# Sheet.net
KiCad netlist of a schematic drawn in Altium Designer
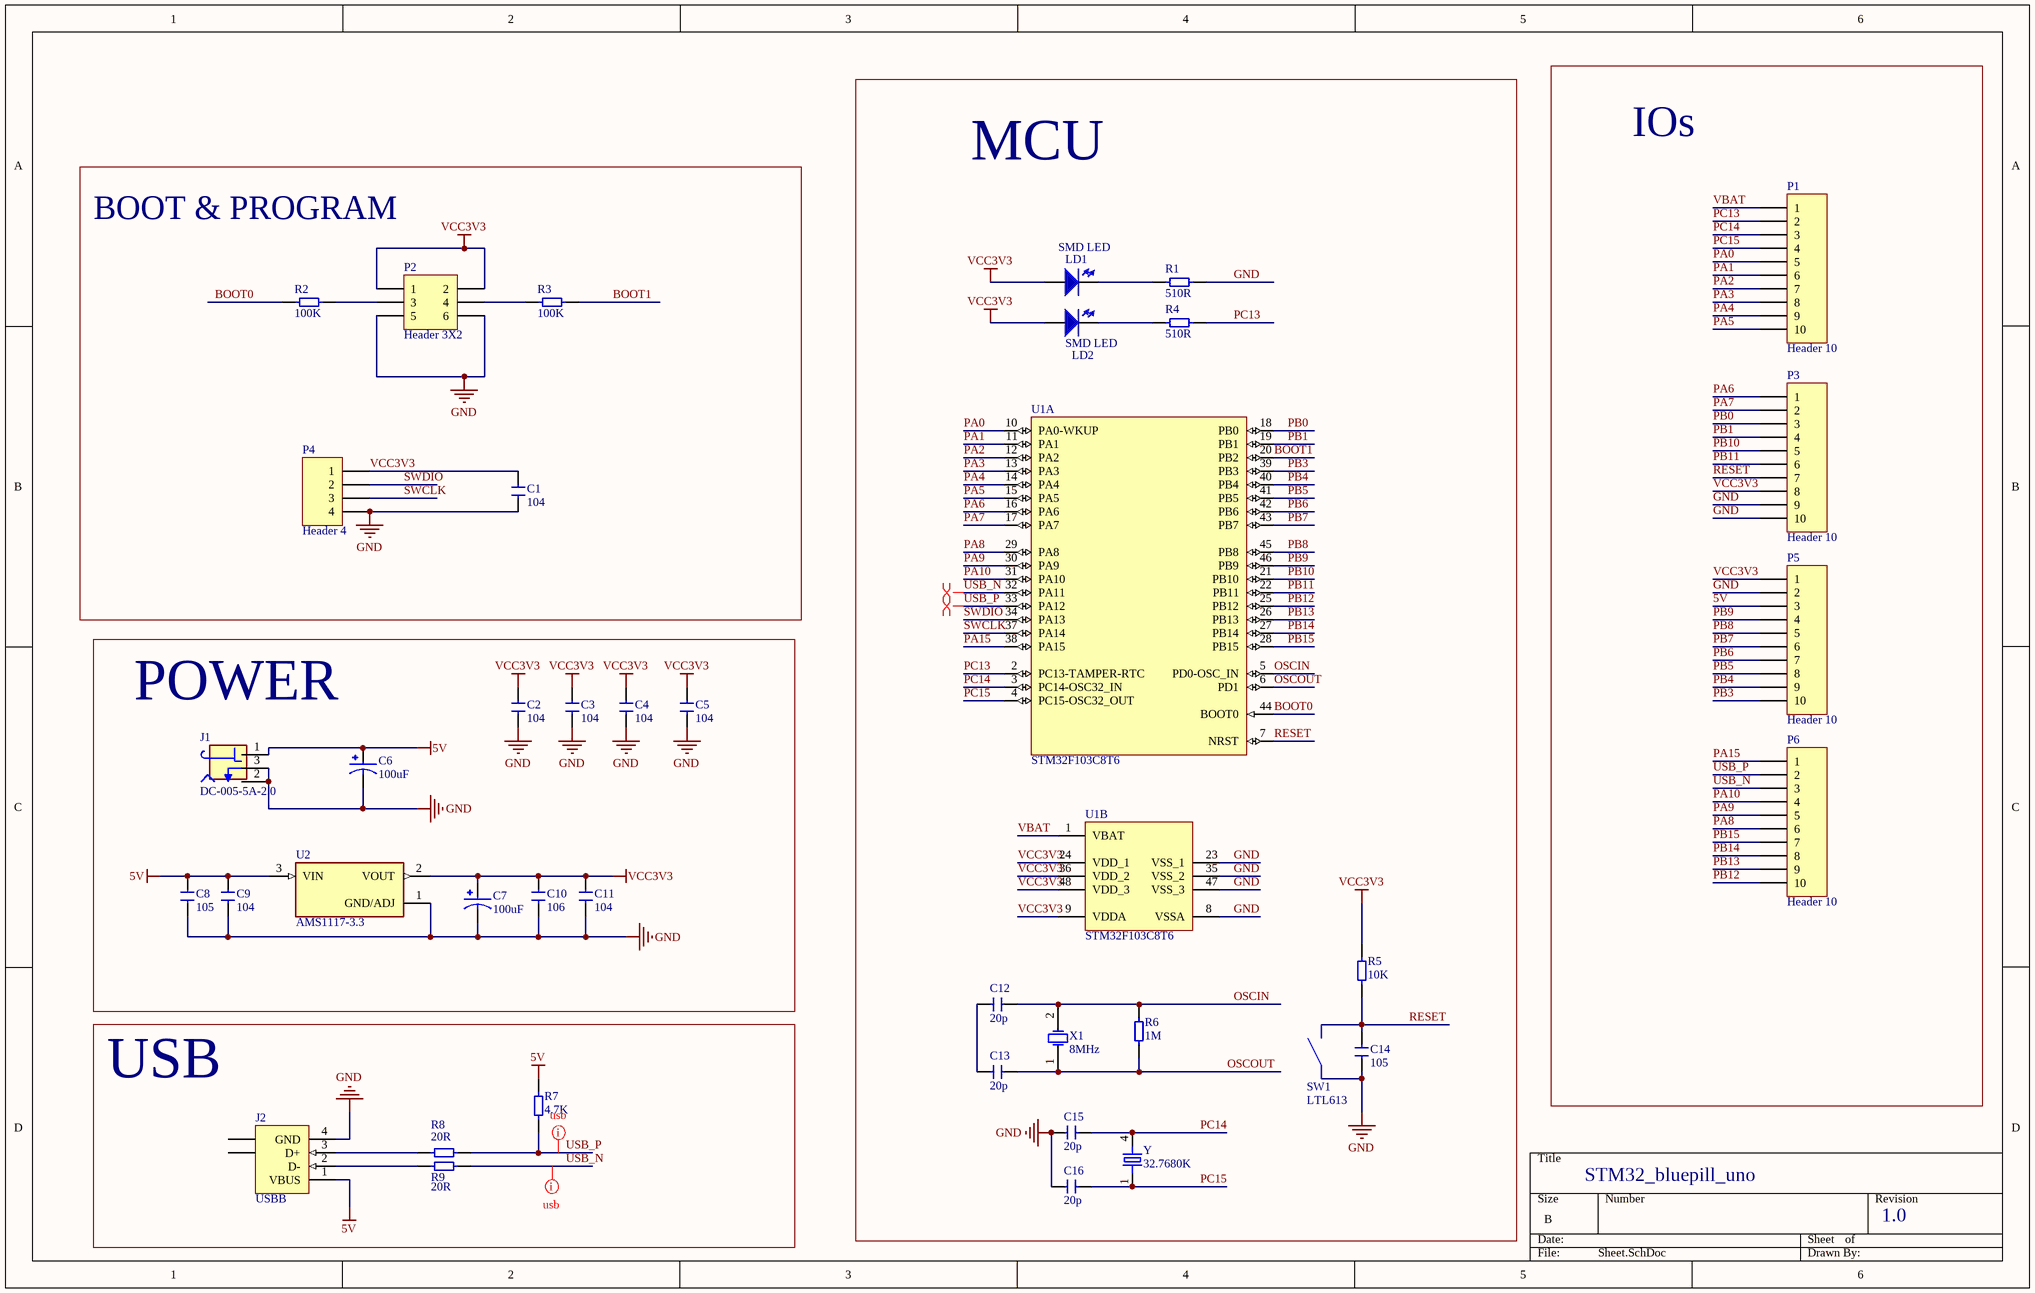
[diagram p0: Sheet.SchDoc]

(export (version "E")
  (design (tool "Eeschema 10.0.6"))
  (components
    (comp (ref "C1")
      (value "Capacitor SMD")
      (footprint "0603 Capacitor")
      (fields (field (name "ALTIUM_UNNAMED_1") "104"))
      (libsource (lib "ZetaBoard_Lib") (part "Capacitor SMD"))
    )
    (comp (ref "C2")
      (value "Capacitor SMD")
      (footprint "0603 Capacitor")
      (fields (field (name "ALTIUM_UNNAMED_1") "104"))
      (libsource (lib "ZetaBoard_Lib") (part "Capacitor SMD"))
    )
    (comp (ref "C3")
      (value "Capacitor SMD")
      (footprint "0603 Capacitor")
      (fields (field (name "ALTIUM_UNNAMED_1") "104"))
      (libsource (lib "ZetaBoard_Lib") (part "Capacitor SMD"))
    )
    (comp (ref "C4")
      (value "Capacitor SMD")
      (footprint "0603 Capacitor")
      (fields (field (name "ALTIUM_UNNAMED_1") "104"))
      (libsource (lib "ZetaBoard_Lib") (part "Capacitor SMD"))
    )
    (comp (ref "C5")
      (value "Capacitor SMD")
      (footprint "0603 Capacitor")
      (fields (field (name "ALTIUM_UNNAMED_1") "104"))
      (libsource (lib "ZetaBoard_Lib") (part "Capacitor SMD"))
    )
    (comp (ref "C6")
      (value "100uF")
      (footprint "CAP_50SVF10M")
      (description "10F 50V Aluminum - Polymer Capacitors Radial, Can - SMD 40mOhm 1000 Hrs @ 125C")
      (fields (field (name "MF") "Panasonic") (field (name "MP") "50SVF10M"))
      (libsource (lib "50SVF10M") (part "50SVF10M"))
    )
    (comp (ref "C7")
      (value "100uF")
      (footprint "CAP_50SVF10M")
      (description "10F 50V Aluminum - Polymer Capacitors Radial, Can - SMD 40mOhm 1000 Hrs @ 125C")
      (fields (field (name "MF") "Panasonic") (field (name "MP") "50SVF10M"))
      (libsource (lib "50SVF10M") (part "50SVF10M"))
    )
    (comp (ref "C8")
      (value "Capacitor SMD")
      (footprint "0603 Capacitor")
      (fields (field (name "ALTIUM_UNNAMED_1") "105"))
      (libsource (lib "ZetaBoard_Lib") (part "Capacitor SMD"))
    )
    (comp (ref "C9")
      (value "Capacitor SMD")
      (footprint "0603 Capacitor")
      (fields (field (name "ALTIUM_UNNAMED_1") "104"))
      (libsource (lib "ZetaBoard_Lib") (part "Capacitor SMD"))
    )
    (comp (ref "C10")
      (value "Capacitor SMD")
      (footprint "0603 Capacitor")
      (fields (field (name "ALTIUM_UNNAMED_1") "106"))
      (libsource (lib "ZetaBoard_Lib") (part "Capacitor SMD"))
    )
    (comp (ref "C11")
      (value "Capacitor SMD")
      (footprint "0603 Capacitor")
      (fields (field (name "ALTIUM_UNNAMED_1") "104"))
      (libsource (lib "ZetaBoard_Lib") (part "Capacitor SMD"))
    )
    (comp (ref "C12")
      (value "Capacitor SMD")
      (footprint "0603 Capacitor")
      (fields (field (name "ALTIUM_UNNAMED_1") "20p"))
      (libsource (lib "ZetaBoard_Lib") (part "Capacitor SMD"))
    )
    (comp (ref "C13")
      (value "Capacitor SMD")
      (footprint "0603 Capacitor")
      (fields (field (name "ALTIUM_UNNAMED_1") "20p"))
      (libsource (lib "ZetaBoard_Lib") (part "Capacitor SMD"))
    )
    (comp (ref "C14")
      (value "Capacitor SMD")
      (footprint "0603 Capacitor")
      (fields (field (name "ALTIUM_UNNAMED_1") "105"))
      (libsource (lib "ZetaBoard_Lib") (part "Capacitor SMD"))
    )
    (comp (ref "C15")
      (value "Capacitor SMD")
      (footprint "0603 Capacitor")
      (fields (field (name "ALTIUM_UNNAMED_1") "20p"))
      (libsource (lib "ZetaBoard_Lib") (part "Capacitor SMD"))
    )
    (comp (ref "C16")
      (value "Capacitor SMD")
      (footprint "0603 Capacitor")
      (fields (field (name "ALTIUM_UNNAMED_1") "20p"))
      (libsource (lib "ZetaBoard_Lib") (part "Capacitor SMD"))
    )
    (comp (ref "J1")
      (value "DC-005-5A-2.0")
      (footprint "XKB_DC-005-5A-2.0")
      (description "DC Power Receptacle Jack, Through Holeï¼ŒRight Angle")
      (fields (field (name "MF") "XKB Industrial Precision"))
      (libsource (lib "DC-005-5A-2.0") (part "DC-005-5A-2.0"))
    )
    (comp (ref "J2")
      (value "USBB")
      (footprint "USB")
      (description "USB 1.1, Right Angle, Thru-Hole, Reverse Type, Receptacle, 4 Position, Black")
      (fields (field (name "PUBLISHER") "Altium Limited"))
      (libsource (lib "My_LIB") (part "USBB"))
    )
    (comp (ref "LD1")
      (value "SMD LED")
      (footprint "LED_1206 RED")
      (libsource (lib "ZetaBoard_Lib") (part "LED SMD"))
    )
    (comp (ref "LD2")
      (value "SMD LED")
      (footprint "LED_1206 RED")
      (libsource (lib "ZetaBoard_Lib") (part "LED SMD"))
    )
    (comp (ref "P1")
      (value "Header 10")
      (footprint "HDR1X10")
      (description "Header, 10-Pin")
      (fields (field (name "PUBLISHER") "Altium Limited"))
      (libsource (lib "Miscellaneous Connectors") (part "Header 10"))
    )
    (comp (ref "P2")
      (value "Header 3X2")
      (footprint "HDR2X3")
      (description "Header, 3-Pin, Dual row")
      (fields (field (name "PUBLISHER") "Altium Limited"))
      (libsource (lib "Miscellaneous Connectors") (part "Header 3X2"))
    )
    (comp (ref "P3")
      (value "Header 10")
      (footprint "HDR1X10")
      (description "Header, 10-Pin")
      (fields (field (name "PUBLISHER") "Altium Limited"))
      (libsource (lib "Miscellaneous Connectors") (part "Header 10"))
    )
    (comp (ref "P4")
      (value "Header 4")
      (footprint "HDR1X4")
      (description "Header, 4-Pin")
      (fields (field (name "PUBLISHER") "Altium Limited"))
      (libsource (lib "Miscellaneous Connectors") (part "Header 4"))
    )
    (comp (ref "P5")
      (value "Header 10")
      (footprint "HDR1X10")
      (description "Header, 10-Pin")
      (fields (field (name "PUBLISHER") "Altium Limited"))
      (libsource (lib "Miscellaneous Connectors") (part "Header 10"))
    )
    (comp (ref "P6")
      (value "Header 10")
      (footprint "HDR1X10")
      (description "Header, 10-Pin")
      (fields (field (name "PUBLISHER") "Altium Limited"))
      (libsource (lib "Miscellaneous Connectors") (part "Header 10"))
    )
    (comp (ref "R1")
      (value "Resistor SMD")
      (footprint "0603 Resistor")
      (fields (field (name "ALTIUM_UNNAMED_1") "510R"))
      (libsource (lib "ZetaBoard_Lib") (part "Resistor SMD"))
    )
    (comp (ref "R2")
      (value "Resistor SMD")
      (footprint "0603 Resistor")
      (fields (field (name "ALTIUM_UNNAMED_1") "100K"))
      (libsource (lib "ZetaBoard_Lib") (part "Resistor SMD"))
    )
    (comp (ref "R3")
      (value "Resistor SMD")
      (footprint "0603 Resistor")
      (fields (field (name "ALTIUM_UNNAMED_1") "100K"))
      (libsource (lib "ZetaBoard_Lib") (part "Resistor SMD"))
    )
    (comp (ref "R4")
      (value "Resistor SMD")
      (footprint "0603 Resistor")
      (fields (field (name "ALTIUM_UNNAMED_1") "510R"))
      (libsource (lib "ZetaBoard_Lib") (part "Resistor SMD"))
    )
    (comp (ref "R5")
      (value "Resistor SMD")
      (footprint "0603 Resistor")
      (fields (field (name "ALTIUM_UNNAMED_1") "10K"))
      (libsource (lib "ZetaBoard_Lib") (part "Resistor SMD"))
    )
    (comp (ref "R6")
      (value "Resistor SMD")
      (footprint "0603 Resistor")
      (fields (field (name "ALTIUM_UNNAMED_1") "1M"))
      (libsource (lib "ZetaBoard_Lib") (part "Resistor SMD"))
    )
    (comp (ref "R7")
      (value "Resistor SMD")
      (footprint "0603 Resistor")
      (fields (field (name "ALTIUM_UNNAMED_1") "4.7K"))
      (libsource (lib "ZetaBoard_Lib") (part "Resistor SMD"))
    )
    (comp (ref "R8")
      (value "Resistor SMD")
      (footprint "0603 Resistor")
      (fields (field (name "ALTIUM_UNNAMED_1") "20R"))
      (libsource (lib "ZetaBoard_Lib") (part "Resistor SMD"))
    )
    (comp (ref "R9")
      (value "Resistor SMD")
      (footprint "0603 Resistor")
      (fields (field (name "ALTIUM_UNNAMED_1") "20R"))
      (libsource (lib "ZetaBoard_Lib") (part "Resistor SMD"))
    )
    (comp (ref "SW1")
      (value "LTL613")
      (footprint "LTL613")
      (description "Tact button switch")
      (libsource (lib "My_LIB") (part "Button_tact"))
    )
    (comp (ref "U1")
      (value "STM32F103C8T6")
      (footprint "LQFP48_N")
      (libsource (lib "STMicroelectronics STM32 F1") (part "STM32F103C8T6"))
    )
    (comp (ref "U2")
      (value "AMS1117-3.3")
      (footprint "SOT229P700X180-4N")
      (description "Sot223/Pkg 1-Amp 3.3-Volt Low Drop Out Voltage Regulatator")
      (fields (field (name "MF") "Advanced Monolithic Systems"))
      (libsource (lib "AMS1117-3.3 (1)") (part "AMS1117-3.3"))
    )
    (comp (ref "X1") (value "8MHz") (footprint "Xtal") (libsource (lib "My_LIB") (part "Crystal")))
    (comp (ref "Y")
      (value "32.7680K")
      (footprint "OSCL550P800X320X254-4N")
      (description "32.768kHz Â±100ppm Crystal 12.5pF 50 kOhms 4-SOJ, 5.50mm pitch")
      (fields (field (name "MP") "MC-306 32.7680K-A5: ROHS") (field (name "MF") "EPSON"))
      (libsource (lib "MC-306_32.7680K-A5__ROHS") (part "MC-306_32.7680K-A5{colon}_ROHS"))
    )
  )
  (nets
    (net (code "1") (name "/BOOT0") (class "Default")
      (node (ref "R2") (pin "1") (pintype "passive"))
      (node (ref "U1") (pin "44") (pinfunction "BOOT0_44") (pintype "input"))
    )
    (net (code "2") (name "/BOOT1") (class "Default")
      (node (ref "R3") (pin "2") (pintype "passive"))
      (node (ref "U1") (pin "20") (pinfunction "PB2_20") (pintype "bidirectional"))
    )
    (net (code "3") (name "/OSCIN") (class "Default")
      (node (ref "C12") (pin "1") (pintype "passive"))
      (node (ref "R6") (pin "2") (pintype "passive"))
      (node (ref "U1") (pin "5") (pinfunction "PD0-OSC_IN_5") (pintype "bidirectional"))
      (node (ref "X1") (pin "2") (pinfunction "OSC2_2") (pintype "passive"))
    )
    (net (code "4") (name "/OSCOUT") (class "Default")
      (node (ref "C13") (pin "1") (pintype "passive"))
      (node (ref "R6") (pin "1") (pintype "passive"))
      (node (ref "U1") (pin "6") (pinfunction "PD1_6") (pintype "bidirectional"))
      (node (ref "X1") (pin "1") (pinfunction "OSC1_1") (pintype "passive"))
    )
    (net (code "5") (name "/PA0") (class "Default")
      (node (ref "P1") (pin "5") (pinfunction "5_5") (pintype "passive"))
      (node (ref "U1") (pin "10") (pinfunction "PA0-WKUP_10") (pintype "bidirectional"))
    )
    (net (code "6") (name "/PA1") (class "Default")
      (node (ref "P1") (pin "6") (pinfunction "6_6") (pintype "passive"))
      (node (ref "U1") (pin "11") (pinfunction "PA1_11") (pintype "bidirectional"))
    )
    (net (code "7") (name "/PA2") (class "Default")
      (node (ref "P1") (pin "7") (pinfunction "7_7") (pintype "passive"))
      (node (ref "U1") (pin "12") (pinfunction "PA2_12") (pintype "bidirectional"))
    )
    (net (code "8") (name "/PA3") (class "Default")
      (node (ref "P1") (pin "8") (pinfunction "8_8") (pintype "passive"))
      (node (ref "U1") (pin "13") (pinfunction "PA3_13") (pintype "bidirectional"))
    )
    (net (code "9") (name "/PA4") (class "Default")
      (node (ref "P1") (pin "9") (pinfunction "9_9") (pintype "passive"))
      (node (ref "U1") (pin "14") (pinfunction "PA4_14") (pintype "bidirectional"))
    )
    (net (code "10") (name "/PA5") (class "Default")
      (node (ref "P1") (pin "10") (pinfunction "10_10") (pintype "passive"))
      (node (ref "U1") (pin "15") (pinfunction "PA5_15") (pintype "bidirectional"))
    )
    (net (code "11") (name "/PA6") (class "Default")
      (node (ref "P3") (pin "1") (pinfunction "1_1") (pintype "passive"))
      (node (ref "U1") (pin "16") (pinfunction "PA6_16") (pintype "bidirectional"))
    )
    (net (code "12") (name "/PA7") (class "Default")
      (node (ref "P3") (pin "2") (pinfunction "2_2") (pintype "passive"))
      (node (ref "U1") (pin "17") (pinfunction "PA7_17") (pintype "bidirectional"))
    )
    (net (code "13") (name "/PA8") (class "Default")
      (node (ref "P6") (pin "6") (pinfunction "6_6") (pintype "passive"))
      (node (ref "U1") (pin "29") (pinfunction "PA8_29") (pintype "bidirectional"))
    )
    (net (code "14") (name "/PA9") (class "Default")
      (node (ref "P6") (pin "5") (pinfunction "5_5") (pintype "passive"))
      (node (ref "U1") (pin "30") (pinfunction "PA9_30") (pintype "bidirectional"))
    )
    (net (code "15") (name "/PA10") (class "Default")
      (node (ref "P6") (pin "4") (pinfunction "4_4") (pintype "passive"))
      (node (ref "U1") (pin "31") (pinfunction "PA10_31") (pintype "bidirectional"))
    )
    (net (code "16") (name "/PA15") (class "Default")
      (node (ref "P6") (pin "1") (pinfunction "1_1") (pintype "passive"))
      (node (ref "U1") (pin "38") (pinfunction "PA15_38") (pintype "bidirectional"))
    )
    (net (code "17") (name "/PB0") (class "Default")
      (node (ref "P3") (pin "3") (pinfunction "3_3") (pintype "passive"))
      (node (ref "U1") (pin "18") (pinfunction "PB0_18") (pintype "bidirectional"))
    )
    (net (code "18") (name "/PB1") (class "Default")
      (node (ref "P3") (pin "4") (pinfunction "4_4") (pintype "passive"))
      (node (ref "U1") (pin "19") (pinfunction "PB1_19") (pintype "bidirectional"))
    )
    (net (code "19") (name "/PB3") (class "Default")
      (node (ref "P5") (pin "10") (pinfunction "10_10") (pintype "passive"))
      (node (ref "U1") (pin "39") (pinfunction "PB3_39") (pintype "bidirectional"))
    )
    (net (code "20") (name "/PB4") (class "Default")
      (node (ref "P5") (pin "9") (pinfunction "9_9") (pintype "passive"))
      (node (ref "U1") (pin "40") (pinfunction "PB4_40") (pintype "bidirectional"))
    )
    (net (code "21") (name "/PB5") (class "Default")
      (node (ref "P5") (pin "8") (pinfunction "8_8") (pintype "passive"))
      (node (ref "U1") (pin "41") (pinfunction "PB5_41") (pintype "bidirectional"))
    )
    (net (code "22") (name "/PB6") (class "Default")
      (node (ref "P5") (pin "7") (pinfunction "7_7") (pintype "passive"))
      (node (ref "U1") (pin "42") (pinfunction "PB6_42") (pintype "bidirectional"))
    )
    (net (code "23") (name "/PB7") (class "Default")
      (node (ref "P5") (pin "6") (pinfunction "6_6") (pintype "passive"))
      (node (ref "U1") (pin "43") (pinfunction "PB7_43") (pintype "bidirectional"))
    )
    (net (code "24") (name "/PB8") (class "Default")
      (node (ref "P5") (pin "5") (pinfunction "5_5") (pintype "passive"))
      (node (ref "U1") (pin "45") (pinfunction "PB8_45") (pintype "bidirectional"))
    )
    (net (code "25") (name "/PB9") (class "Default")
      (node (ref "P5") (pin "4") (pinfunction "4_4") (pintype "passive"))
      (node (ref "U1") (pin "46") (pinfunction "PB9_46") (pintype "bidirectional"))
    )
    (net (code "26") (name "/PB10") (class "Default")
      (node (ref "P3") (pin "5") (pinfunction "5_5") (pintype "passive"))
      (node (ref "U1") (pin "21") (pinfunction "PB10_21") (pintype "bidirectional"))
    )
    (net (code "27") (name "/PB11") (class "Default")
      (node (ref "P3") (pin "6") (pinfunction "6_6") (pintype "passive"))
      (node (ref "U1") (pin "22") (pinfunction "PB11_22") (pintype "bidirectional"))
    )
    (net (code "28") (name "/PB12") (class "Default")
      (node (ref "P6") (pin "10") (pinfunction "10_10") (pintype "passive"))
      (node (ref "U1") (pin "25") (pinfunction "PB12_25") (pintype "bidirectional"))
    )
    (net (code "29") (name "/PB13") (class "Default")
      (node (ref "P6") (pin "9") (pinfunction "9_9") (pintype "passive"))
      (node (ref "U1") (pin "26") (pinfunction "PB13_26") (pintype "bidirectional"))
    )
    (net (code "30") (name "/PB14") (class "Default")
      (node (ref "P6") (pin "8") (pinfunction "8_8") (pintype "passive"))
      (node (ref "U1") (pin "27") (pinfunction "PB14_27") (pintype "bidirectional"))
    )
    (net (code "31") (name "/PB15") (class "Default")
      (node (ref "P6") (pin "7") (pinfunction "7_7") (pintype "passive"))
      (node (ref "U1") (pin "28") (pinfunction "PB15_28") (pintype "bidirectional"))
    )
    (net (code "32") (name "/PC13") (class "Default")
      (node (ref "P1") (pin "2") (pinfunction "2_2") (pintype "passive"))
      (node (ref "R4") (pin "2") (pintype "passive"))
      (node (ref "U1") (pin "2") (pinfunction "PC13-TAMPER-RTC_2") (pintype "bidirectional"))
    )
    (net (code "33") (name "/PC14") (class "Default")
      (node (ref "C15") (pin "1") (pintype "passive"))
      (node (ref "P1") (pin "3") (pinfunction "3_3") (pintype "passive"))
      (node (ref "U1") (pin "3") (pinfunction "PC14-OSC32_IN_3") (pintype "bidirectional"))
      (node (ref "Y") (pin "4") (pinfunction "4_4") (pintype "passive"))
    )
    (net (code "34") (name "/PC15") (class "Default")
      (node (ref "C16") (pin "1") (pintype "passive"))
      (node (ref "P1") (pin "4") (pinfunction "4_4") (pintype "passive"))
      (node (ref "U1") (pin "4") (pinfunction "PC15-OSC32_OUT_4") (pintype "bidirectional"))
      (node (ref "Y") (pin "1") (pinfunction "1_1") (pintype "passive"))
    )
    (net (code "35") (name "/RESET") (class "Default")
      (node (ref "C14") (pin "2") (pintype "passive"))
      (node (ref "P3") (pin "7") (pinfunction "7_7") (pintype "passive"))
      (node (ref "R5") (pin "1") (pintype "passive"))
      (node (ref "SW1") (pin "1") (pinfunction "1_1") (pintype "passive"))
      (node (ref "U1") (pin "7") (pinfunction "NRST_7") (pintype "bidirectional"))
    )
    (net (code "36") (name "/SWCLK") (class "Default")
      (node (ref "P4") (pin "3") (pinfunction "3_3") (pintype "passive"))
      (node (ref "U1") (pin "37") (pinfunction "PA14_37") (pintype "bidirectional"))
    )
    (net (code "37") (name "/SWDIO") (class "Default")
      (node (ref "P4") (pin "2") (pinfunction "2_2") (pintype "passive"))
      (node (ref "U1") (pin "34") (pinfunction "PA13_34") (pintype "bidirectional"))
    )
    (net (code "38") (name "/USB_N") (class "Default")
      (node (ref "P6") (pin "3") (pinfunction "3_3") (pintype "passive"))
      (node (ref "R9") (pin "2") (pintype "passive"))
      (node (ref "U1") (pin "32") (pinfunction "PA11_32") (pintype "bidirectional"))
    )
    (net (code "39") (name "/USB_P") (class "Default")
      (node (ref "P6") (pin "2") (pinfunction "2_2") (pintype "passive"))
      (node (ref "R7") (pin "1") (pintype "passive"))
      (node (ref "R8") (pin "2") (pintype "passive"))
      (node (ref "U1") (pin "33") (pinfunction "PA12_33") (pintype "bidirectional"))
    )
    (net (code "40") (name "/VBAT") (class "Default")
      (node (ref "P1") (pin "1") (pinfunction "1_1") (pintype "passive"))
      (node (ref "U1") (pin "1") (pinfunction "VBAT_1") (pintype "power_in"))
    )
    (net (code "41") (name "5V") (class "Default")
      (node (ref "C6") (pin "1") (pinfunction "1_1") (pintype "passive"))
      (node (ref "C8") (pin "2") (pintype "passive"))
      (node (ref "C9") (pin "2") (pintype "passive"))
      (node (ref "J1") (pin "1") (pinfunction "1_1") (pintype "passive"))
      (node (ref "J2") (pin "1") (pinfunction "VBUS_1") (pintype "power_in"))
      (node (ref "P5") (pin "3") (pinfunction "3_3") (pintype "passive"))
      (node (ref "R7") (pin "2") (pintype "passive"))
      (node (ref "U2") (pin "3") (pinfunction "VIN_3") (pintype "input"))
    )
    (net (code "42") (name "GND") (class "Default")
      (node (ref "C1") (pin "1") (pintype "passive"))
      (node (ref "C10") (pin "1") (pintype "passive"))
      (node (ref "C11") (pin "1") (pintype "passive"))
      (node (ref "C14") (pin "1") (pintype "passive"))
      (node (ref "C15") (pin "2") (pintype "passive"))
      (node (ref "C16") (pin "2") (pintype "passive"))
      (node (ref "C2") (pin "1") (pintype "passive"))
      (node (ref "C3") (pin "1") (pintype "passive"))
      (node (ref "C4") (pin "1") (pintype "passive"))
      (node (ref "C5") (pin "1") (pintype "passive"))
      (node (ref "C6") (pin "2") (pinfunction "2_2") (pintype "passive"))
      (node (ref "C7") (pin "2") (pinfunction "2_2") (pintype "passive"))
      (node (ref "C8") (pin "1") (pintype "passive"))
      (node (ref "C9") (pin "1") (pintype "passive"))
      (node (ref "J1") (pin "2") (pinfunction "2_2") (pintype "passive"))
      (node (ref "J1") (pin "3") (pinfunction "3_3") (pintype "passive"))
      (node (ref "J2") (pin "4") (pinfunction "GND_4") (pintype "power_in"))
      (node (ref "P2") (pin "5") (pinfunction "5_5") (pintype "passive"))
      (node (ref "P2") (pin "6") (pinfunction "6_6") (pintype "passive"))
      (node (ref "P3") (pin "10") (pinfunction "10_10") (pintype "passive"))
      (node (ref "P3") (pin "9") (pinfunction "9_9") (pintype "passive"))
      (node (ref "P4") (pin "4") (pinfunction "4_4") (pintype "passive"))
      (node (ref "P5") (pin "2") (pinfunction "2_2") (pintype "passive"))
      (node (ref "R1") (pin "2") (pintype "passive"))
      (node (ref "SW1") (pin "0") (pinfunction "0_0") (pintype "passive"))
      (node (ref "U1") (pin "23") (pinfunction "VSS_1_23") (pintype "power_in"))
      (node (ref "U1") (pin "35") (pinfunction "VSS_2_35") (pintype "power_in"))
      (node (ref "U1") (pin "47") (pinfunction "VSS_3_47") (pintype "power_in"))
      (node (ref "U1") (pin "8") (pinfunction "VSSA_8") (pintype "power_in"))
      (node (ref "U2") (pin "1") (pinfunction "GND/ADJ_1") (pintype "power_in"))
    )
    (net (code "43") (name "Net-(C12-Pad2)") (class "Default")
      (node (ref "C12") (pin "2") (pintype "passive"))
      (node (ref "C13") (pin "2") (pintype "passive"))
    )
    (net (code "44") (name "Net-(J2-D+)") (class "Default")
      (node (ref "J2") (pin "3") (pinfunction "D+_3") (pintype "input"))
      (node (ref "R8") (pin "1") (pintype "passive"))
    )
    (net (code "45") (name "Net-(J2-D-)") (class "Default")
      (node (ref "J2") (pin "2") (pinfunction "D-_2") (pintype "input"))
      (node (ref "R9") (pin "1") (pintype "passive"))
    )
    (net (code "46") (name "Net-(LD1-K)") (class "Default")
      (node (ref "LD1") (pin "2") (pinfunction "K_2") (pintype "passive"))
      (node (ref "R1") (pin "1") (pintype "passive"))
    )
    (net (code "47") (name "Net-(LD2-K)") (class "Default")
      (node (ref "LD2") (pin "2") (pinfunction "K_2") (pintype "passive"))
      (node (ref "R4") (pin "1") (pintype "passive"))
    )
    (net (code "48") (name "Net-(P2-Pad3)") (class "Default")
      (node (ref "P2") (pin "3") (pinfunction "3_3") (pintype "passive"))
      (node (ref "R2") (pin "2") (pintype "passive"))
    )
    (net (code "49") (name "Net-(P2-Pad4)") (class "Default")
      (node (ref "P2") (pin "4") (pinfunction "4_4") (pintype "passive"))
      (node (ref "R3") (pin "1") (pintype "passive"))
    )
    (net (code "50") (name "VCC3V3") (class "Default")
      (node (ref "C1") (pin "2") (pintype "passive"))
      (node (ref "C10") (pin "2") (pintype "passive"))
      (node (ref "C11") (pin "2") (pintype "passive"))
      (node (ref "C2") (pin "2") (pintype "passive"))
      (node (ref "C3") (pin "2") (pintype "passive"))
      (node (ref "C4") (pin "2") (pintype "passive"))
      (node (ref "C5") (pin "2") (pintype "passive"))
      (node (ref "C7") (pin "1") (pinfunction "1_1") (pintype "passive"))
      (node (ref "LD1") (pin "1") (pinfunction "A_1") (pintype "passive"))
      (node (ref "LD2") (pin "1") (pinfunction "A_1") (pintype "passive"))
      (node (ref "P2") (pin "1") (pinfunction "1_1") (pintype "passive"))
      (node (ref "P2") (pin "2") (pinfunction "2_2") (pintype "passive"))
      (node (ref "P3") (pin "8") (pinfunction "8_8") (pintype "passive"))
      (node (ref "P4") (pin "1") (pinfunction "1_1") (pintype "passive"))
      (node (ref "P5") (pin "1") (pinfunction "1_1") (pintype "passive"))
      (node (ref "R5") (pin "2") (pintype "passive"))
      (node (ref "U1") (pin "24") (pinfunction "VDD_1_24") (pintype "power_in"))
      (node (ref "U1") (pin "36") (pinfunction "VDD_2_36") (pintype "power_in"))
      (node (ref "U1") (pin "48") (pinfunction "VDD_3_48") (pintype "power_in"))
      (node (ref "U1") (pin "9") (pinfunction "VDDA_9") (pintype "power_in"))
      (node (ref "U2") (pin "2") (pinfunction "VOUT_2") (pintype "output"))
    )
    (net (code "51") (name "unconnected-(J2-SHLD-Pad5)") (class "Default")
      (node (ref "J2") (pin "5") (pinfunction "SHLD_5") (pintype "passive"))
    )
    (net (code "52") (name "unconnected-(J2-SHLD-Pad6)") (class "Default")
      (node (ref "J2") (pin "6") (pinfunction "SHLD_6") (pintype "passive"))
    )
  )
)
